# business_card_v1.net
KiCad netlist of a schematic drawn in EAGLE
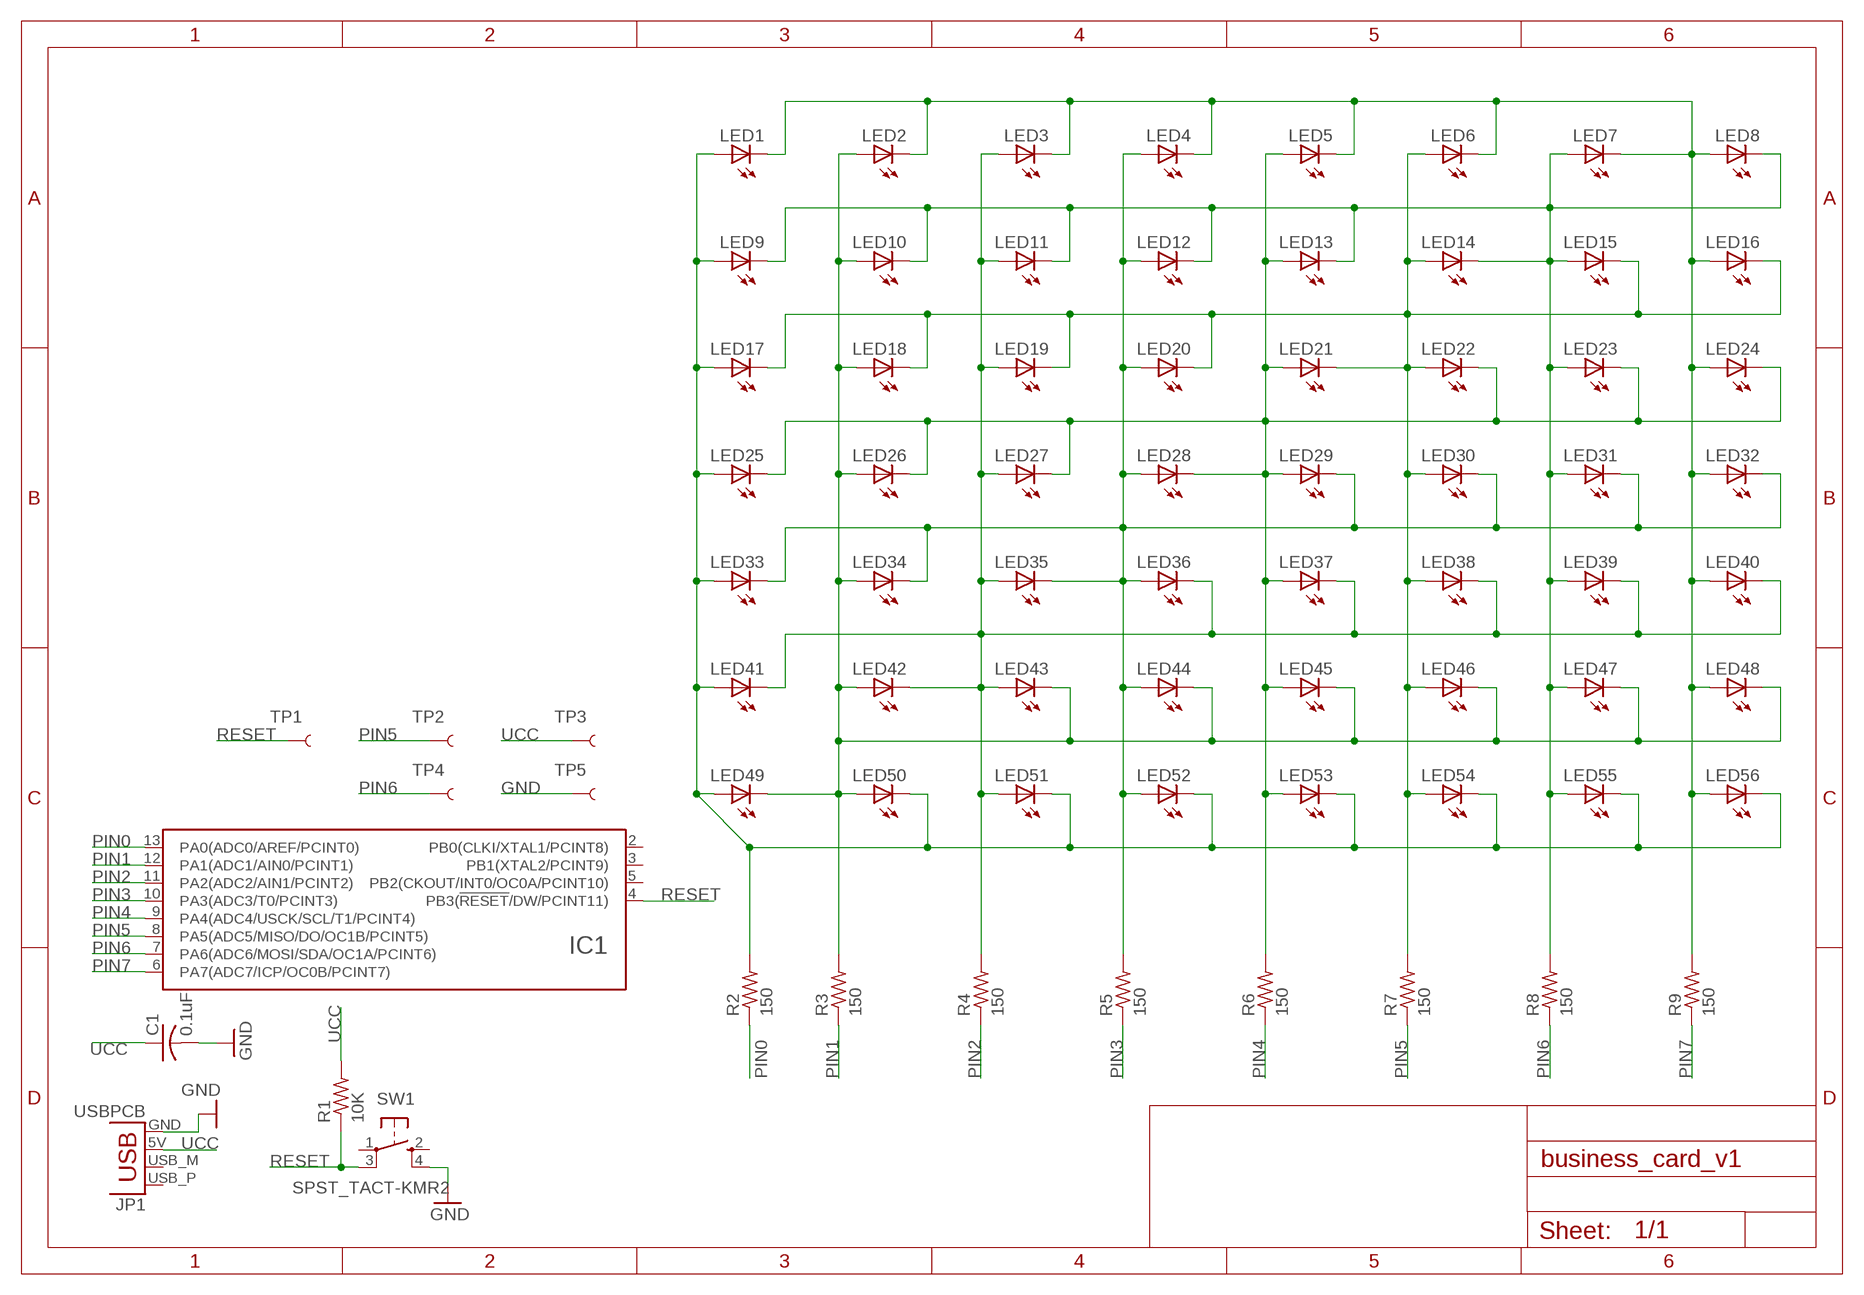
[diagram p0: schematic, sheet 1]

(export (version "E")
  (design (tool "Eeschema 10.0.6"))
  (components
    (comp (ref "C1")
      (value "0.1uF")
      (footprint "eagle-import:C0603K")
      (libsource (lib "eagle-import") (part "C-USC0603K"))
    )
    (comp (ref "IC1")
      (value "ATTINY24/44/84-SSU")
      (footprint "eagle-import:SOIC14")
      (libsource (lib "eagle-import") (part "ATTINY24/44/84-SSU"))
    )
    (comp (ref "JP1")
      (value "USBPCB")
      (footprint "eagle-import:USB-A-PCB")
      (libsource (lib "eagle-import") (part "USBPCB"))
    )
    (comp (ref "LED1")
      (value "LEDCHIPLED_0805")
      (footprint "eagle-import:CHIPLED_0805")
      (libsource (lib "eagle-import") (part "LEDCHIPLED_0805"))
    )
    (comp (ref "LED2")
      (value "LEDCHIPLED_0805")
      (footprint "eagle-import:CHIPLED_0805")
      (libsource (lib "eagle-import") (part "LEDCHIPLED_0805"))
    )
    (comp (ref "LED3")
      (value "LEDCHIPLED_0805")
      (footprint "eagle-import:CHIPLED_0805")
      (libsource (lib "eagle-import") (part "LEDCHIPLED_0805"))
    )
    (comp (ref "LED4")
      (value "LEDCHIPLED_0805")
      (footprint "eagle-import:CHIPLED_0805")
      (libsource (lib "eagle-import") (part "LEDCHIPLED_0805"))
    )
    (comp (ref "LED5")
      (value "LEDCHIPLED_0805")
      (footprint "eagle-import:CHIPLED_0805")
      (libsource (lib "eagle-import") (part "LEDCHIPLED_0805"))
    )
    (comp (ref "LED6")
      (value "LEDCHIPLED_0805")
      (footprint "eagle-import:CHIPLED_0805")
      (libsource (lib "eagle-import") (part "LEDCHIPLED_0805"))
    )
    (comp (ref "LED7")
      (value "LEDCHIPLED_0805")
      (footprint "eagle-import:CHIPLED_0805")
      (libsource (lib "eagle-import") (part "LEDCHIPLED_0805"))
    )
    (comp (ref "LED8")
      (value "LEDCHIPLED_0805")
      (footprint "eagle-import:CHIPLED_0805")
      (libsource (lib "eagle-import") (part "LEDCHIPLED_0805"))
    )
    (comp (ref "LED9")
      (value "LEDCHIPLED_0805")
      (footprint "eagle-import:CHIPLED_0805")
      (libsource (lib "eagle-import") (part "LEDCHIPLED_0805"))
    )
    (comp (ref "LED10")
      (value "LEDCHIPLED_0805")
      (footprint "eagle-import:CHIPLED_0805")
      (libsource (lib "eagle-import") (part "LEDCHIPLED_0805"))
    )
    (comp (ref "LED11")
      (value "LEDCHIPLED_0805")
      (footprint "eagle-import:CHIPLED_0805")
      (libsource (lib "eagle-import") (part "LEDCHIPLED_0805"))
    )
    (comp (ref "LED12")
      (value "LEDCHIPLED_0805")
      (footprint "eagle-import:CHIPLED_0805")
      (libsource (lib "eagle-import") (part "LEDCHIPLED_0805"))
    )
    (comp (ref "LED13")
      (value "LEDCHIPLED_0805")
      (footprint "eagle-import:CHIPLED_0805")
      (libsource (lib "eagle-import") (part "LEDCHIPLED_0805"))
    )
    (comp (ref "LED14")
      (value "LEDCHIPLED_0805")
      (footprint "eagle-import:CHIPLED_0805")
      (libsource (lib "eagle-import") (part "LEDCHIPLED_0805"))
    )
    (comp (ref "LED15")
      (value "LEDCHIPLED_0805")
      (footprint "eagle-import:CHIPLED_0805")
      (libsource (lib "eagle-import") (part "LEDCHIPLED_0805"))
    )
    (comp (ref "LED16")
      (value "LEDCHIPLED_0805")
      (footprint "eagle-import:CHIPLED_0805")
      (libsource (lib "eagle-import") (part "LEDCHIPLED_0805"))
    )
    (comp (ref "LED17")
      (value "LEDCHIPLED_0805")
      (footprint "eagle-import:CHIPLED_0805")
      (libsource (lib "eagle-import") (part "LEDCHIPLED_0805"))
    )
    (comp (ref "LED18")
      (value "LEDCHIPLED_0805")
      (footprint "eagle-import:CHIPLED_0805")
      (libsource (lib "eagle-import") (part "LEDCHIPLED_0805"))
    )
    (comp (ref "LED19")
      (value "LEDCHIPLED_0805")
      (footprint "eagle-import:CHIPLED_0805")
      (libsource (lib "eagle-import") (part "LEDCHIPLED_0805"))
    )
    (comp (ref "LED20")
      (value "LEDCHIPLED_0805")
      (footprint "eagle-import:CHIPLED_0805")
      (libsource (lib "eagle-import") (part "LEDCHIPLED_0805"))
    )
    (comp (ref "LED21")
      (value "LEDCHIPLED_0805")
      (footprint "eagle-import:CHIPLED_0805")
      (libsource (lib "eagle-import") (part "LEDCHIPLED_0805"))
    )
    (comp (ref "LED22")
      (value "LEDCHIPLED_0805")
      (footprint "eagle-import:CHIPLED_0805")
      (libsource (lib "eagle-import") (part "LEDCHIPLED_0805"))
    )
    (comp (ref "LED23")
      (value "LEDCHIPLED_0805")
      (footprint "eagle-import:CHIPLED_0805")
      (libsource (lib "eagle-import") (part "LEDCHIPLED_0805"))
    )
    (comp (ref "LED24")
      (value "LEDCHIPLED_0805")
      (footprint "eagle-import:CHIPLED_0805")
      (libsource (lib "eagle-import") (part "LEDCHIPLED_0805"))
    )
    (comp (ref "LED25")
      (value "LEDCHIPLED_0805")
      (footprint "eagle-import:CHIPLED_0805")
      (libsource (lib "eagle-import") (part "LEDCHIPLED_0805"))
    )
    (comp (ref "LED26")
      (value "LEDCHIPLED_0805")
      (footprint "eagle-import:CHIPLED_0805")
      (libsource (lib "eagle-import") (part "LEDCHIPLED_0805"))
    )
    (comp (ref "LED27")
      (value "LEDCHIPLED_0805")
      (footprint "eagle-import:CHIPLED_0805")
      (libsource (lib "eagle-import") (part "LEDCHIPLED_0805"))
    )
    (comp (ref "LED28")
      (value "LEDCHIPLED_0805")
      (footprint "eagle-import:CHIPLED_0805")
      (libsource (lib "eagle-import") (part "LEDCHIPLED_0805"))
    )
    (comp (ref "LED29")
      (value "LEDCHIPLED_0805")
      (footprint "eagle-import:CHIPLED_0805")
      (libsource (lib "eagle-import") (part "LEDCHIPLED_0805"))
    )
    (comp (ref "LED30")
      (value "LEDCHIPLED_0805")
      (footprint "eagle-import:CHIPLED_0805")
      (libsource (lib "eagle-import") (part "LEDCHIPLED_0805"))
    )
    (comp (ref "LED31")
      (value "LEDCHIPLED_0805")
      (footprint "eagle-import:CHIPLED_0805")
      (libsource (lib "eagle-import") (part "LEDCHIPLED_0805"))
    )
    (comp (ref "LED32")
      (value "LEDCHIPLED_0805")
      (footprint "eagle-import:CHIPLED_0805")
      (libsource (lib "eagle-import") (part "LEDCHIPLED_0805"))
    )
    (comp (ref "LED33")
      (value "LEDCHIPLED_0805")
      (footprint "eagle-import:CHIPLED_0805")
      (libsource (lib "eagle-import") (part "LEDCHIPLED_0805"))
    )
    (comp (ref "LED34")
      (value "LEDCHIPLED_0805")
      (footprint "eagle-import:CHIPLED_0805")
      (libsource (lib "eagle-import") (part "LEDCHIPLED_0805"))
    )
    (comp (ref "LED35")
      (value "LEDCHIPLED_0805")
      (footprint "eagle-import:CHIPLED_0805")
      (libsource (lib "eagle-import") (part "LEDCHIPLED_0805"))
    )
    (comp (ref "LED36")
      (value "LEDCHIPLED_0805")
      (footprint "eagle-import:CHIPLED_0805")
      (libsource (lib "eagle-import") (part "LEDCHIPLED_0805"))
    )
    (comp (ref "LED37")
      (value "LEDCHIPLED_0805")
      (footprint "eagle-import:CHIPLED_0805")
      (libsource (lib "eagle-import") (part "LEDCHIPLED_0805"))
    )
    (comp (ref "LED38")
      (value "LEDCHIPLED_0805")
      (footprint "eagle-import:CHIPLED_0805")
      (libsource (lib "eagle-import") (part "LEDCHIPLED_0805"))
    )
    (comp (ref "LED39")
      (value "LEDCHIPLED_0805")
      (footprint "eagle-import:CHIPLED_0805")
      (libsource (lib "eagle-import") (part "LEDCHIPLED_0805"))
    )
    (comp (ref "LED40")
      (value "LEDCHIPLED_0805")
      (footprint "eagle-import:CHIPLED_0805")
      (libsource (lib "eagle-import") (part "LEDCHIPLED_0805"))
    )
    (comp (ref "LED41")
      (value "LEDCHIPLED_0805")
      (footprint "eagle-import:CHIPLED_0805")
      (libsource (lib "eagle-import") (part "LEDCHIPLED_0805"))
    )
    (comp (ref "LED42")
      (value "LEDCHIPLED_0805")
      (footprint "eagle-import:CHIPLED_0805")
      (libsource (lib "eagle-import") (part "LEDCHIPLED_0805"))
    )
    (comp (ref "LED43")
      (value "LEDCHIPLED_0805")
      (footprint "eagle-import:CHIPLED_0805")
      (libsource (lib "eagle-import") (part "LEDCHIPLED_0805"))
    )
    (comp (ref "LED44")
      (value "LEDCHIPLED_0805")
      (footprint "eagle-import:CHIPLED_0805")
      (libsource (lib "eagle-import") (part "LEDCHIPLED_0805"))
    )
    (comp (ref "LED45")
      (value "LEDCHIPLED_0805")
      (footprint "eagle-import:CHIPLED_0805")
      (libsource (lib "eagle-import") (part "LEDCHIPLED_0805"))
    )
    (comp (ref "LED46")
      (value "LEDCHIPLED_0805")
      (footprint "eagle-import:CHIPLED_0805")
      (libsource (lib "eagle-import") (part "LEDCHIPLED_0805"))
    )
    (comp (ref "LED47")
      (value "LEDCHIPLED_0805")
      (footprint "eagle-import:CHIPLED_0805")
      (libsource (lib "eagle-import") (part "LEDCHIPLED_0805"))
    )
    (comp (ref "LED48")
      (value "LEDCHIPLED_0805")
      (footprint "eagle-import:CHIPLED_0805")
      (libsource (lib "eagle-import") (part "LEDCHIPLED_0805"))
    )
    (comp (ref "LED49")
      (value "LEDCHIPLED_0805")
      (footprint "eagle-import:CHIPLED_0805")
      (libsource (lib "eagle-import") (part "LEDCHIPLED_0805"))
    )
    (comp (ref "LED50")
      (value "LEDCHIPLED_0805")
      (footprint "eagle-import:CHIPLED_0805")
      (libsource (lib "eagle-import") (part "LEDCHIPLED_0805"))
    )
    (comp (ref "LED51")
      (value "LEDCHIPLED_0805")
      (footprint "eagle-import:CHIPLED_0805")
      (libsource (lib "eagle-import") (part "LEDCHIPLED_0805"))
    )
    (comp (ref "LED52")
      (value "LEDCHIPLED_0805")
      (footprint "eagle-import:CHIPLED_0805")
      (libsource (lib "eagle-import") (part "LEDCHIPLED_0805"))
    )
    (comp (ref "LED53")
      (value "LEDCHIPLED_0805")
      (footprint "eagle-import:CHIPLED_0805")
      (libsource (lib "eagle-import") (part "LEDCHIPLED_0805"))
    )
    (comp (ref "LED54")
      (value "LEDCHIPLED_0805")
      (footprint "eagle-import:CHIPLED_0805")
      (libsource (lib "eagle-import") (part "LEDCHIPLED_0805"))
    )
    (comp (ref "LED55")
      (value "LEDCHIPLED_0805")
      (footprint "eagle-import:CHIPLED_0805")
      (libsource (lib "eagle-import") (part "LEDCHIPLED_0805"))
    )
    (comp (ref "LED56")
      (value "LEDCHIPLED_0805")
      (footprint "eagle-import:CHIPLED_0805")
      (libsource (lib "eagle-import") (part "LEDCHIPLED_0805"))
    )
    (comp (ref "R1")
      (value "10K")
      (footprint "eagle-import:R0603")
      (libsource (lib "eagle-import") (part "R-US_R0603"))
    )
    (comp (ref "R2")
      (value "150")
      (footprint "eagle-import:R0603")
      (libsource (lib "eagle-import") (part "R-US_R0603"))
    )
    (comp (ref "R3")
      (value "150")
      (footprint "eagle-import:R0603")
      (libsource (lib "eagle-import") (part "R-US_R0603"))
    )
    (comp (ref "R4")
      (value "150")
      (footprint "eagle-import:R0603")
      (libsource (lib "eagle-import") (part "R-US_R0603"))
    )
    (comp (ref "R5")
      (value "150")
      (footprint "eagle-import:R0603")
      (libsource (lib "eagle-import") (part "R-US_R0603"))
    )
    (comp (ref "R6")
      (value "150")
      (footprint "eagle-import:R0603")
      (libsource (lib "eagle-import") (part "R-US_R0603"))
    )
    (comp (ref "R7")
      (value "150")
      (footprint "eagle-import:R0603")
      (libsource (lib "eagle-import") (part "R-US_R0603"))
    )
    (comp (ref "R8")
      (value "150")
      (footprint "eagle-import:R0603")
      (libsource (lib "eagle-import") (part "R-US_R0603"))
    )
    (comp (ref "R9")
      (value "150")
      (footprint "eagle-import:R0603")
      (libsource (lib "eagle-import") (part "R-US_R0603"))
    )
    (comp (ref "SW1")
      (value "SPST_TACT-KMR2")
      (footprint "eagle-import:KMR2")
      (libsource (lib "eagle-import") (part "SPST_TACT-KMR2"))
    )
    (comp (ref "TP1")
      (value "TEST-POINTPOGO_PTH")
      (footprint "eagle-import:1X01_NO_SILK")
      (libsource (lib "eagle-import") (part "TEST-POINTPOGO_PTH"))
    )
    (comp (ref "TP2")
      (value "TEST-POINTPOGO_PTH")
      (footprint "eagle-import:1X01_NO_SILK")
      (libsource (lib "eagle-import") (part "TEST-POINTPOGO_PTH"))
    )
    (comp (ref "TP3")
      (value "TEST-POINTPOGO_PTH")
      (footprint "eagle-import:1X01_NO_SILK")
      (libsource (lib "eagle-import") (part "TEST-POINTPOGO_PTH"))
    )
    (comp (ref "TP4")
      (value "TEST-POINTPOGO_PTH")
      (footprint "eagle-import:1X01_NO_SILK")
      (libsource (lib "eagle-import") (part "TEST-POINTPOGO_PTH"))
    )
    (comp (ref "TP5")
      (value "TEST-POINTPOGO_PTH")
      (footprint "eagle-import:1X01_NO_SILK")
      (libsource (lib "eagle-import") (part "TEST-POINTPOGO_PTH"))
    )
  )
  (nets
    (net (code "1") (name "/PIN0") (class "Default")
      (node (ref "IC1") (pin "13") (pinfunction "PA0(ADC0/AREF/PCINT0)_13") (pintype "bidirectional"))
      (node (ref "R2") (pin "1") (pinfunction "1_1") (pintype "passive"))
    )
    (net (code "2") (name "/PIN1") (class "Default")
      (node (ref "IC1") (pin "12") (pinfunction "PA1(ADC1/AIN0/PCINT1)_12") (pintype "bidirectional"))
      (node (ref "R3") (pin "1") (pinfunction "1_1") (pintype "passive"))
    )
    (net (code "3") (name "/PIN2") (class "Default")
      (node (ref "IC1") (pin "11") (pinfunction "PA2(ADC2/AIN1/PCINT2)_11") (pintype "bidirectional"))
      (node (ref "R4") (pin "1") (pinfunction "1_1") (pintype "passive"))
    )
    (net (code "4") (name "/PIN3") (class "Default")
      (node (ref "IC1") (pin "10") (pinfunction "PA3(ADC3/T0/PCINT3)_10") (pintype "bidirectional"))
      (node (ref "R5") (pin "1") (pinfunction "1_1") (pintype "passive"))
    )
    (net (code "5") (name "/PIN4") (class "Default")
      (node (ref "IC1") (pin "9") (pinfunction "PA4(ADC4/USCK/SCL/T1/PCINT4)_9") (pintype "bidirectional"))
      (node (ref "R6") (pin "1") (pinfunction "1_1") (pintype "passive"))
    )
    (net (code "6") (name "/PIN5") (class "Default")
      (node (ref "IC1") (pin "8") (pinfunction "PA5(ADC5/MISO/DO/OC1B/PCINT5)_8") (pintype "bidirectional"))
      (node (ref "R7") (pin "1") (pinfunction "1_1") (pintype "passive"))
      (node (ref "TP2") (pin "1") (pinfunction "1_1") (pintype "bidirectional"))
    )
    (net (code "7") (name "/PIN6") (class "Default")
      (node (ref "IC1") (pin "7") (pinfunction "PA6(ADC6/MOSI/SDA/OC1A/PCINT6)_7") (pintype "bidirectional"))
      (node (ref "R8") (pin "1") (pinfunction "1_1") (pintype "passive"))
      (node (ref "TP4") (pin "1") (pinfunction "1_1") (pintype "bidirectional"))
    )
    (net (code "8") (name "/PIN7") (class "Default")
      (node (ref "IC1") (pin "6") (pinfunction "PA7(ADC7/ICP/OC0B/PCINT7)_6") (pintype "bidirectional"))
      (node (ref "R9") (pin "1") (pinfunction "1_1") (pintype "passive"))
    )
    (net (code "9") (name "/RESET") (class "Default")
      (node (ref "IC1") (pin "4") (pinfunction "PB3(~{RESET}/DW/PCINT11)_4") (pintype "bidirectional"))
      (node (ref "R1") (pin "1") (pinfunction "1_1") (pintype "passive"))
      (node (ref "SW1") (pin "3") (pinfunction "P1_3") (pintype "passive"))
      (node (ref "TP1") (pin "1") (pinfunction "1_1") (pintype "bidirectional"))
    )
    (net (code "10") (name "/UCC") (class "Default")
      (node (ref "C1") (pin "1") (pinfunction "1_1") (pintype "passive"))
      (node (ref "JP1") (pin "5V") (pinfunction "VBUS_5V") (pintype "bidirectional"))
      (node (ref "R1") (pin "2") (pinfunction "2_2") (pintype "passive"))
      (node (ref "TP3") (pin "1") (pinfunction "1_1") (pintype "bidirectional"))
    )
    (net (code "11") (name "GND") (class "Default")
      (node (ref "C1") (pin "2") (pinfunction "2_2") (pintype "passive"))
      (node (ref "JP1") (pin "GND") (pinfunction "GND_GND") (pintype "bidirectional"))
      (node (ref "SW1") (pin "4") (pinfunction "S1_4") (pintype "passive"))
      (node (ref "TP5") (pin "1") (pinfunction "1_1") (pintype "bidirectional"))
    )
    (net (code "12") (name "Net-(LED1-PadA)") (class "Default")
      (node (ref "LED1") (pin "A") (pinfunction "A_A") (pintype "passive"))
      (node (ref "LED17") (pin "A") (pinfunction "A_A") (pintype "passive"))
      (node (ref "LED25") (pin "A") (pinfunction "A_A") (pintype "passive"))
      (node (ref "LED33") (pin "A") (pinfunction "A_A") (pintype "passive"))
      (node (ref "LED41") (pin "A") (pinfunction "A_A") (pintype "passive"))
      (node (ref "LED49") (pin "A") (pinfunction "A_A") (pintype "passive"))
      (node (ref "LED50") (pin "C") (pinfunction "C_C") (pintype "passive"))
      (node (ref "LED51") (pin "C") (pinfunction "C_C") (pintype "passive"))
      (node (ref "LED52") (pin "C") (pinfunction "C_C") (pintype "passive"))
      (node (ref "LED53") (pin "C") (pinfunction "C_C") (pintype "passive"))
      (node (ref "LED54") (pin "C") (pinfunction "C_C") (pintype "passive"))
      (node (ref "LED55") (pin "C") (pinfunction "C_C") (pintype "passive"))
      (node (ref "LED56") (pin "C") (pinfunction "C_C") (pintype "passive"))
      (node (ref "LED9") (pin "A") (pinfunction "A_A") (pintype "passive"))
      (node (ref "R2") (pin "2") (pinfunction "2_2") (pintype "passive"))
    )
    (net (code "13") (name "Net-(LED1-PadC)") (class "Default")
      (node (ref "LED1") (pin "C") (pinfunction "C_C") (pintype "passive"))
      (node (ref "LED16") (pin "A") (pinfunction "A_A") (pintype "passive"))
      (node (ref "LED2") (pin "C") (pinfunction "C_C") (pintype "passive"))
      (node (ref "LED24") (pin "A") (pinfunction "A_A") (pintype "passive"))
      (node (ref "LED3") (pin "C") (pinfunction "C_C") (pintype "passive"))
      (node (ref "LED32") (pin "A") (pinfunction "A_A") (pintype "passive"))
      (node (ref "LED4") (pin "C") (pinfunction "C_C") (pintype "passive"))
      (node (ref "LED40") (pin "A") (pinfunction "A_A") (pintype "passive"))
      (node (ref "LED48") (pin "A") (pinfunction "A_A") (pintype "passive"))
      (node (ref "LED5") (pin "C") (pinfunction "C_C") (pintype "passive"))
      (node (ref "LED56") (pin "A") (pinfunction "A_A") (pintype "passive"))
      (node (ref "LED6") (pin "C") (pinfunction "C_C") (pintype "passive"))
      (node (ref "LED7") (pin "C") (pinfunction "C_C") (pintype "passive"))
      (node (ref "LED8") (pin "A") (pinfunction "A_A") (pintype "passive"))
      (node (ref "R9") (pin "2") (pinfunction "2_2") (pintype "passive"))
    )
    (net (code "14") (name "Net-(LED10-PadA)") (class "Default")
      (node (ref "LED10") (pin "A") (pinfunction "A_A") (pintype "passive"))
      (node (ref "LED18") (pin "A") (pinfunction "A_A") (pintype "passive"))
      (node (ref "LED2") (pin "A") (pinfunction "A_A") (pintype "passive"))
      (node (ref "LED26") (pin "A") (pinfunction "A_A") (pintype "passive"))
      (node (ref "LED34") (pin "A") (pinfunction "A_A") (pintype "passive"))
      (node (ref "LED42") (pin "A") (pinfunction "A_A") (pintype "passive"))
      (node (ref "LED43") (pin "C") (pinfunction "C_C") (pintype "passive"))
      (node (ref "LED44") (pin "C") (pinfunction "C_C") (pintype "passive"))
      (node (ref "LED45") (pin "C") (pinfunction "C_C") (pintype "passive"))
      (node (ref "LED46") (pin "C") (pinfunction "C_C") (pintype "passive"))
      (node (ref "LED47") (pin "C") (pinfunction "C_C") (pintype "passive"))
      (node (ref "LED48") (pin "C") (pinfunction "C_C") (pintype "passive"))
      (node (ref "LED49") (pin "C") (pinfunction "C_C") (pintype "passive"))
      (node (ref "LED50") (pin "A") (pinfunction "A_A") (pintype "passive"))
      (node (ref "R3") (pin "2") (pinfunction "2_2") (pintype "passive"))
    )
    (net (code "15") (name "Net-(LED10-PadC)") (class "Default")
      (node (ref "LED10") (pin "C") (pinfunction "C_C") (pintype "passive"))
      (node (ref "LED11") (pin "C") (pinfunction "C_C") (pintype "passive"))
      (node (ref "LED12") (pin "C") (pinfunction "C_C") (pintype "passive"))
      (node (ref "LED13") (pin "C") (pinfunction "C_C") (pintype "passive"))
      (node (ref "LED14") (pin "C") (pinfunction "C_C") (pintype "passive"))
      (node (ref "LED15") (pin "A") (pinfunction "A_A") (pintype "passive"))
      (node (ref "LED23") (pin "A") (pinfunction "A_A") (pintype "passive"))
      (node (ref "LED31") (pin "A") (pinfunction "A_A") (pintype "passive"))
      (node (ref "LED39") (pin "A") (pinfunction "A_A") (pintype "passive"))
      (node (ref "LED47") (pin "A") (pinfunction "A_A") (pintype "passive"))
      (node (ref "LED55") (pin "A") (pinfunction "A_A") (pintype "passive"))
      (node (ref "LED7") (pin "A") (pinfunction "A_A") (pintype "passive"))
      (node (ref "LED8") (pin "C") (pinfunction "C_C") (pintype "passive"))
      (node (ref "LED9") (pin "C") (pinfunction "C_C") (pintype "passive"))
      (node (ref "R8") (pin "2") (pinfunction "2_2") (pintype "passive"))
    )
    (net (code "16") (name "Net-(LED11-PadA)") (class "Default")
      (node (ref "LED11") (pin "A") (pinfunction "A_A") (pintype "passive"))
      (node (ref "LED19") (pin "A") (pinfunction "A_A") (pintype "passive"))
      (node (ref "LED27") (pin "A") (pinfunction "A_A") (pintype "passive"))
      (node (ref "LED3") (pin "A") (pinfunction "A_A") (pintype "passive"))
      (node (ref "LED35") (pin "A") (pinfunction "A_A") (pintype "passive"))
      (node (ref "LED36") (pin "C") (pinfunction "C_C") (pintype "passive"))
      (node (ref "LED37") (pin "C") (pinfunction "C_C") (pintype "passive"))
      (node (ref "LED38") (pin "C") (pinfunction "C_C") (pintype "passive"))
      (node (ref "LED39") (pin "C") (pinfunction "C_C") (pintype "passive"))
      (node (ref "LED40") (pin "C") (pinfunction "C_C") (pintype "passive"))
      (node (ref "LED41") (pin "C") (pinfunction "C_C") (pintype "passive"))
      (node (ref "LED42") (pin "C") (pinfunction "C_C") (pintype "passive"))
      (node (ref "LED43") (pin "A") (pinfunction "A_A") (pintype "passive"))
      (node (ref "LED51") (pin "A") (pinfunction "A_A") (pintype "passive"))
      (node (ref "R4") (pin "2") (pinfunction "2_2") (pintype "passive"))
    )
    (net (code "17") (name "Net-(LED12-PadA)") (class "Default")
      (node (ref "LED12") (pin "A") (pinfunction "A_A") (pintype "passive"))
      (node (ref "LED20") (pin "A") (pinfunction "A_A") (pintype "passive"))
      (node (ref "LED28") (pin "A") (pinfunction "A_A") (pintype "passive"))
      (node (ref "LED29") (pin "C") (pinfunction "C_C") (pintype "passive"))
      (node (ref "LED30") (pin "C") (pinfunction "C_C") (pintype "passive"))
      (node (ref "LED31") (pin "C") (pinfunction "C_C") (pintype "passive"))
      (node (ref "LED32") (pin "C") (pinfunction "C_C") (pintype "passive"))
      (node (ref "LED33") (pin "C") (pinfunction "C_C") (pintype "passive"))
      (node (ref "LED34") (pin "C") (pinfunction "C_C") (pintype "passive"))
      (node (ref "LED35") (pin "C") (pinfunction "C_C") (pintype "passive"))
      (node (ref "LED36") (pin "A") (pinfunction "A_A") (pintype "passive"))
      (node (ref "LED4") (pin "A") (pinfunction "A_A") (pintype "passive"))
      (node (ref "LED44") (pin "A") (pinfunction "A_A") (pintype "passive"))
      (node (ref "LED52") (pin "A") (pinfunction "A_A") (pintype "passive"))
      (node (ref "R5") (pin "2") (pinfunction "2_2") (pintype "passive"))
    )
    (net (code "18") (name "Net-(LED13-PadA)") (class "Default")
      (node (ref "LED13") (pin "A") (pinfunction "A_A") (pintype "passive"))
      (node (ref "LED21") (pin "A") (pinfunction "A_A") (pintype "passive"))
      (node (ref "LED22") (pin "C") (pinfunction "C_C") (pintype "passive"))
      (node (ref "LED23") (pin "C") (pinfunction "C_C") (pintype "passive"))
      (node (ref "LED24") (pin "C") (pinfunction "C_C") (pintype "passive"))
      (node (ref "LED25") (pin "C") (pinfunction "C_C") (pintype "passive"))
      (node (ref "LED26") (pin "C") (pinfunction "C_C") (pintype "passive"))
      (node (ref "LED27") (pin "C") (pinfunction "C_C") (pintype "passive"))
      (node (ref "LED28") (pin "C") (pinfunction "C_C") (pintype "passive"))
      (node (ref "LED29") (pin "A") (pinfunction "A_A") (pintype "passive"))
      (node (ref "LED37") (pin "A") (pinfunction "A_A") (pintype "passive"))
      (node (ref "LED45") (pin "A") (pinfunction "A_A") (pintype "passive"))
      (node (ref "LED5") (pin "A") (pinfunction "A_A") (pintype "passive"))
      (node (ref "LED53") (pin "A") (pinfunction "A_A") (pintype "passive"))
      (node (ref "R6") (pin "2") (pinfunction "2_2") (pintype "passive"))
    )
    (net (code "19") (name "Net-(LED14-PadA)") (class "Default")
      (node (ref "LED14") (pin "A") (pinfunction "A_A") (pintype "passive"))
      (node (ref "LED15") (pin "C") (pinfunction "C_C") (pintype "passive"))
      (node (ref "LED16") (pin "C") (pinfunction "C_C") (pintype "passive"))
      (node (ref "LED17") (pin "C") (pinfunction "C_C") (pintype "passive"))
      (node (ref "LED18") (pin "C") (pinfunction "C_C") (pintype "passive"))
      (node (ref "LED19") (pin "C") (pinfunction "C_C") (pintype "passive"))
      (node (ref "LED20") (pin "C") (pinfunction "C_C") (pintype "passive"))
      (node (ref "LED21") (pin "C") (pinfunction "C_C") (pintype "passive"))
      (node (ref "LED22") (pin "A") (pinfunction "A_A") (pintype "passive"))
      (node (ref "LED30") (pin "A") (pinfunction "A_A") (pintype "passive"))
      (node (ref "LED38") (pin "A") (pinfunction "A_A") (pintype "passive"))
      (node (ref "LED46") (pin "A") (pinfunction "A_A") (pintype "passive"))
      (node (ref "LED54") (pin "A") (pinfunction "A_A") (pintype "passive"))
      (node (ref "LED6") (pin "A") (pinfunction "A_A") (pintype "passive"))
      (node (ref "R7") (pin "2") (pinfunction "2_2") (pintype "passive"))
    )
    (net (code "20") (name "unconnected-(IC1A-PB0(CLKI{slash}XTAL1{slash}PCINT8)-Pad2)") (class "Default")
      (node (ref "IC1") (pin "2") (pinfunction "PB0(CLKI/XTAL1/PCINT8)_2") (pintype "bidirectional"))
    )
    (net (code "21") (name "unconnected-(IC1A-PB1(XTAL2{slash}PCINT9)-Pad3)") (class "Default")
      (node (ref "IC1") (pin "3") (pinfunction "PB1(XTAL2/PCINT9)_3") (pintype "bidirectional"))
    )
    (net (code "22") (name "unconnected-(IC1A-PB2(CKOUT{slash}INT0{slash}OC0A{slash}PCINT10)-Pad5)") (class "Default")
      (node (ref "IC1") (pin "5") (pinfunction "PB2(CKOUT/INT0/OC0A/PCINT10)_5") (pintype "bidirectional"))
    )
    (net (code "23") (name "unconnected-(JP1-D+-PadUSB_P)") (class "Default")
      (node (ref "JP1") (pin "USB_P") (pinfunction "D+_USB_P") (pintype "bidirectional"))
    )
    (net (code "24") (name "unconnected-(JP1-D--PadUSB_M)") (class "Default")
      (node (ref "JP1") (pin "USB_M") (pinfunction "D-_USB_M") (pintype "bidirectional"))
    )
    (net (code "25") (name "unconnected-(SW1-P-Pad1)") (class "Default")
      (node (ref "SW1") (pin "1") (pinfunction "P_1") (pintype "passive"))
    )
    (net (code "26") (name "unconnected-(SW1-S-Pad2)") (class "Default")
      (node (ref "SW1") (pin "2") (pinfunction "S_2") (pintype "passive"))
    )
  )
)
